# Adafruit_Feather_M0_Adalogger.net
KiCad netlist of a schematic drawn in EAGLE
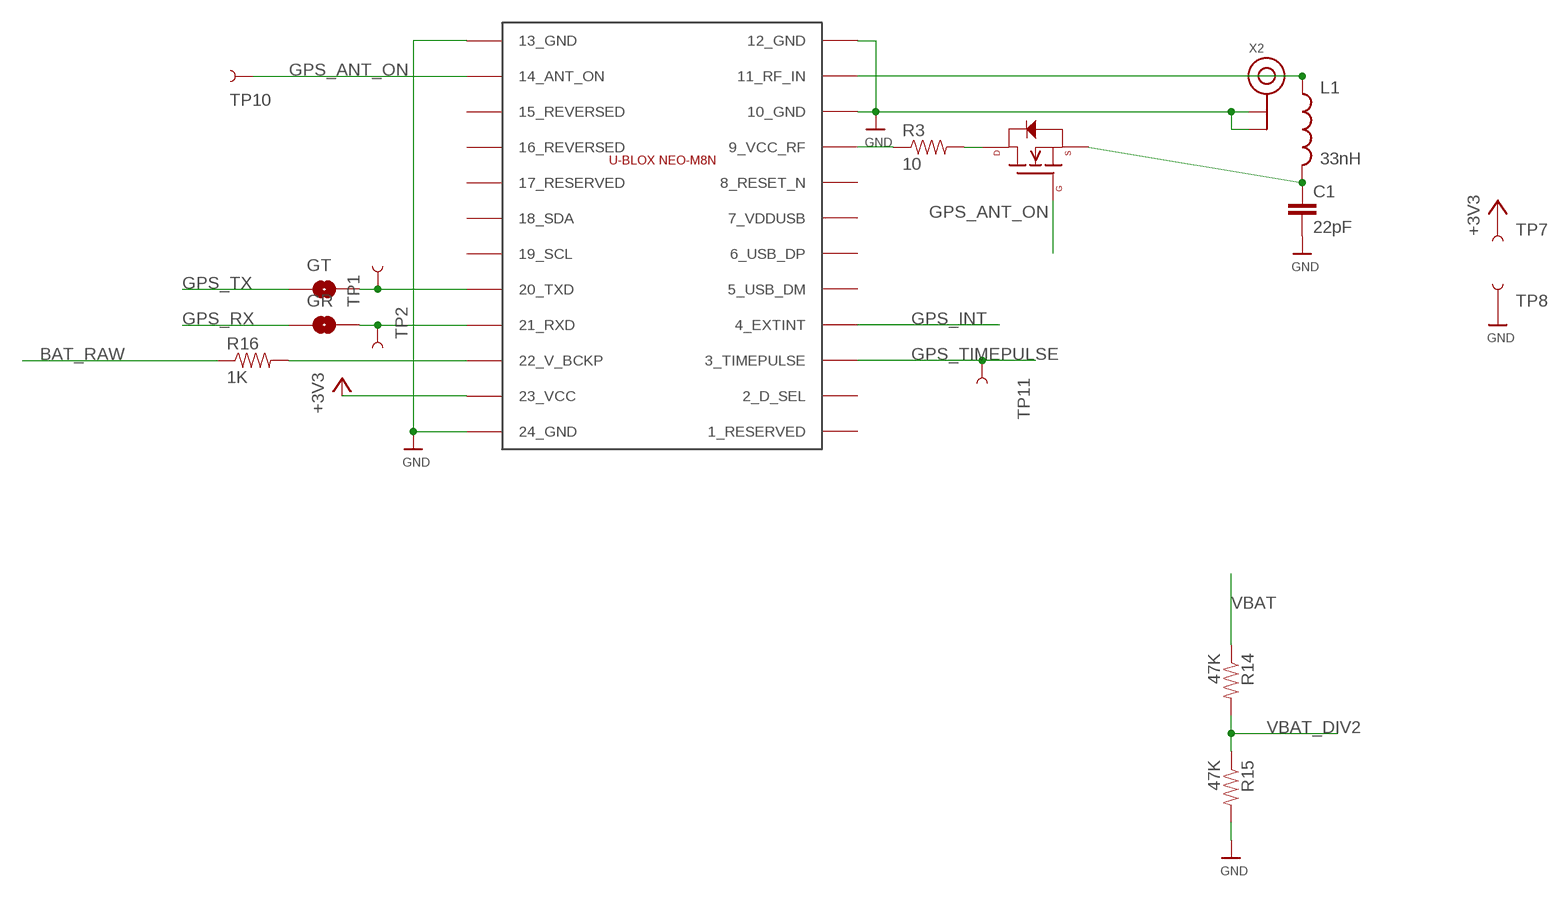
[diagram p0: schematic, sheet 1, part 1 of 2]
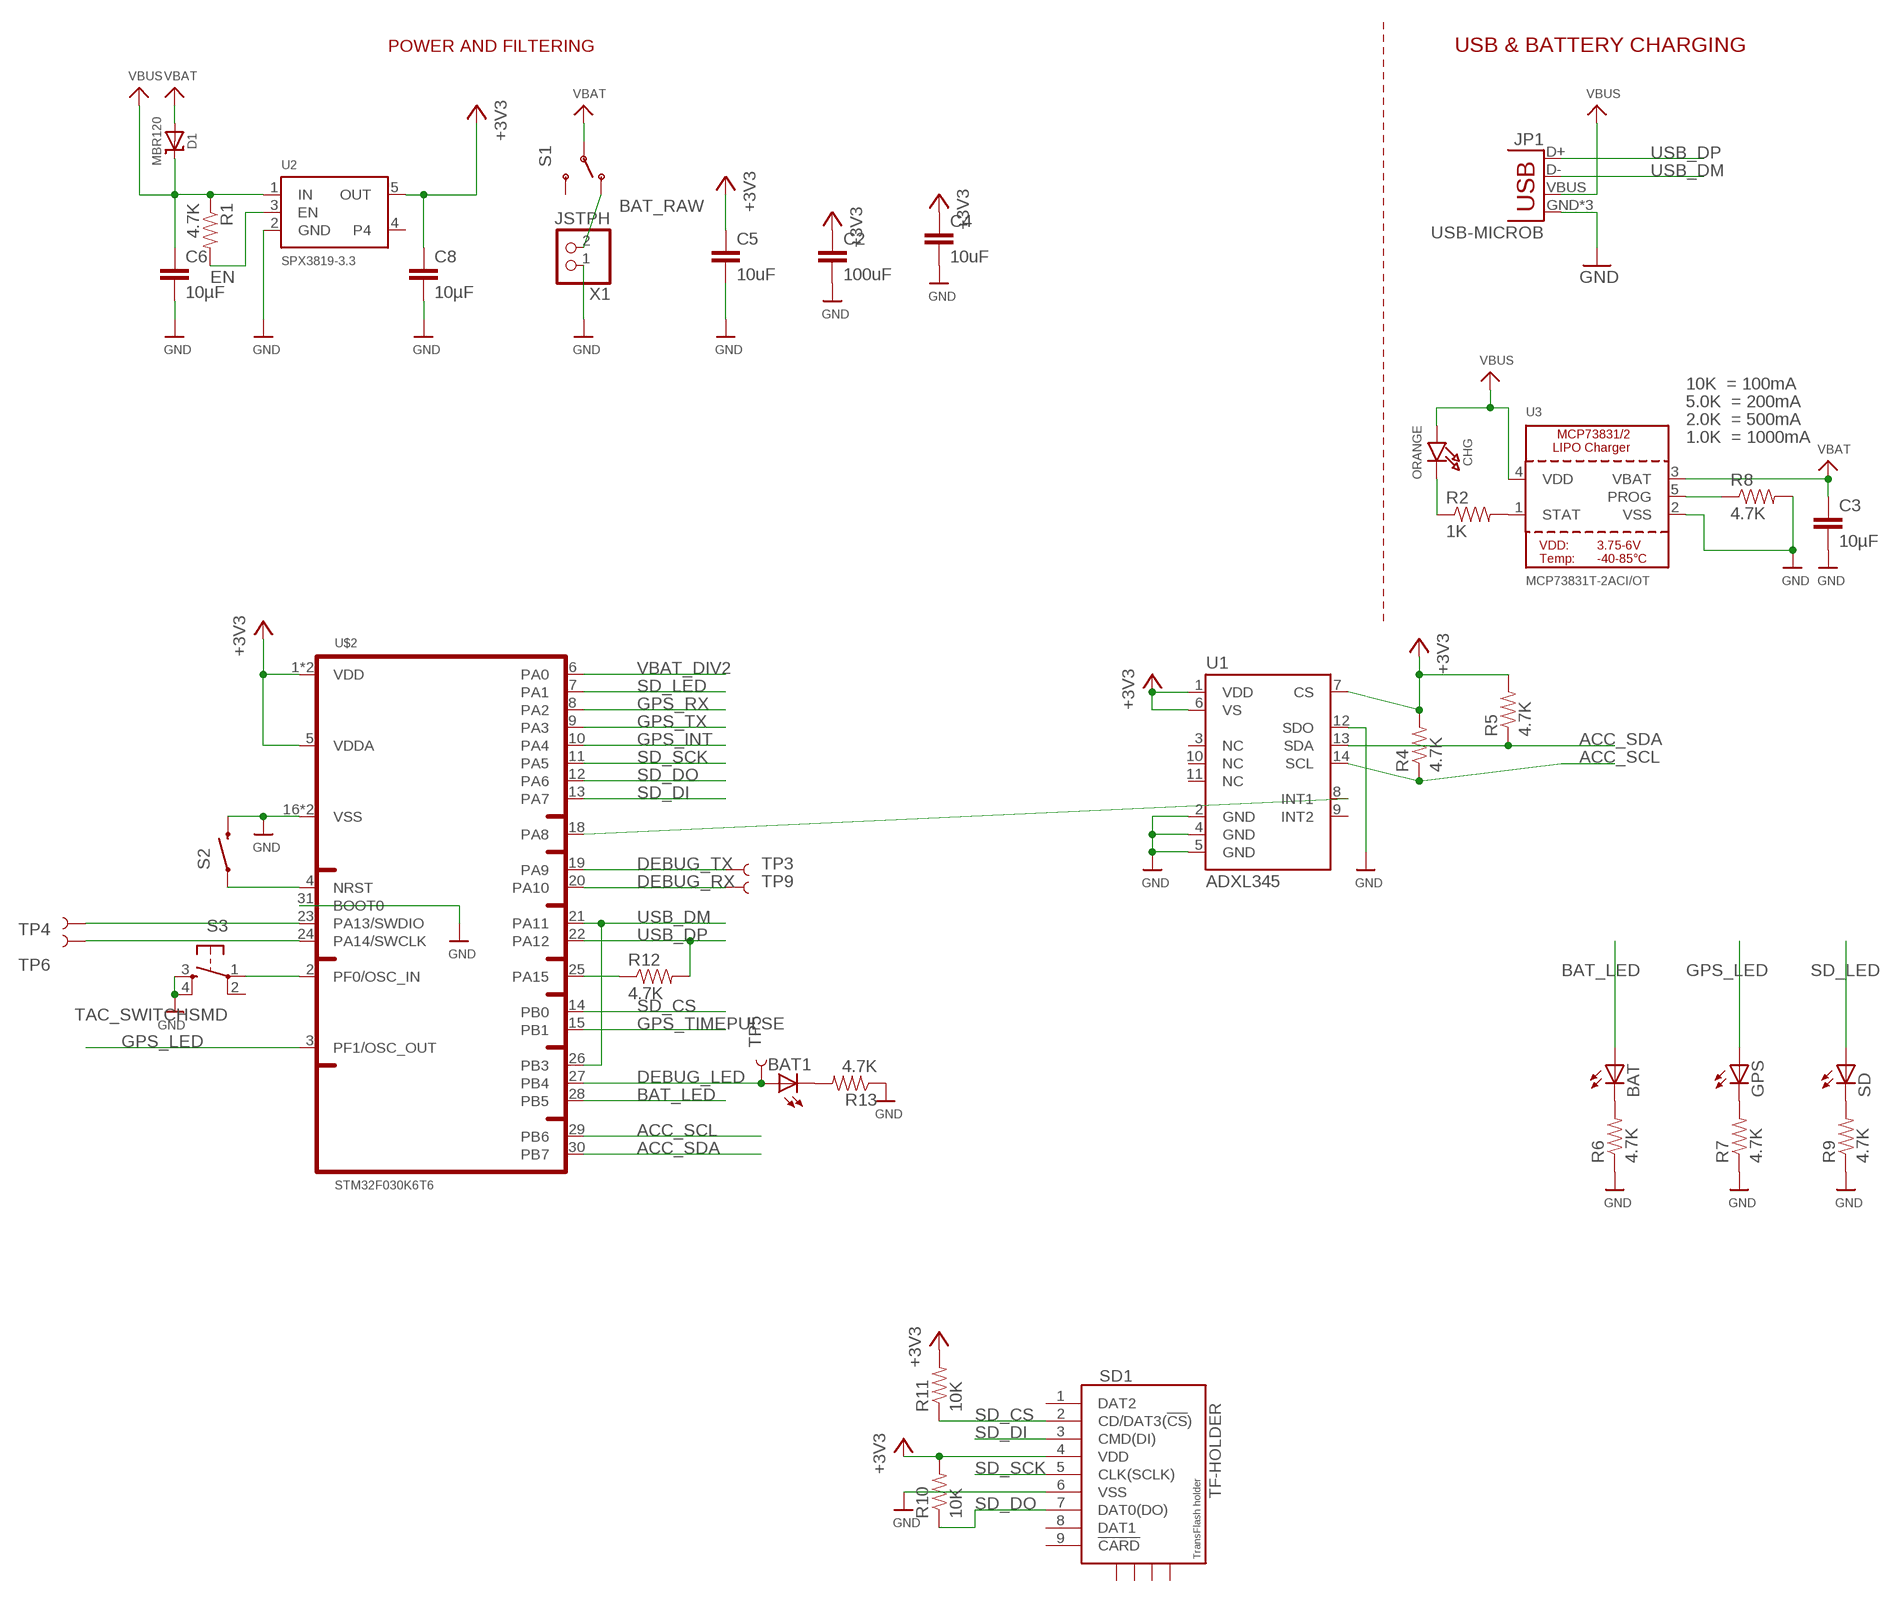
[diagram p1: schematic, sheet 1, part 2 of 2]

(export (version "E")
  (design (tool "Eeschema 10.0.6"))
  (components
    (comp (ref "BAT")
      (value "LEDCHIPLED_0805")
      (footprint "eagle-import:CHIPLED_0805")
      (libsource (lib "eagle-import") (part "LEDCHIPLED_0805"))
    )
    (comp (ref "BAT1")
      (value "LEDCHIPLED_0805")
      (footprint "eagle-import:CHIPLED_0805")
      (libsource (lib "eagle-import") (part "LEDCHIPLED_0805"))
    )
    (comp (ref "C1")
      (value "22pF")
      (footprint "eagle-import:0805")
      (libsource (lib "eagle-import") (part "CAP0805"))
    )
    (comp (ref "C2")
      (value "100uF")
      (footprint "eagle-import:1210")
      (libsource (lib "eagle-import") (part "100UF6.3V20%(1210)"))
    )
    (comp (ref "C3")
      (value "10µF")
      (footprint "eagle-import:0805")
      (libsource (lib "eagle-import") (part "CAP0805"))
    )
    (comp (ref "C4")
      (value "10uF")
      (footprint "eagle-import:0805")
      (libsource (lib "eagle-import") (part "CAP0805"))
    )
    (comp (ref "C5")
      (value "10uF")
      (footprint "eagle-import:0805")
      (libsource (lib "eagle-import") (part "CAP0805"))
    )
    (comp (ref "C6")
      (value "10µF")
      (footprint "eagle-import:0805")
      (libsource (lib "eagle-import") (part "CAP0805"))
    )
    (comp (ref "C8")
      (value "10µF")
      (footprint "eagle-import:0805")
      (libsource (lib "eagle-import") (part "CAP0805"))
    )
    (comp (ref "CHG")
      (value "ORANGE")
      (footprint "eagle-import:CHIPLED_0805_NOOUTLINE")
      (libsource (lib "eagle-import") (part "LED0805_NOOUTLINE"))
    )
    (comp (ref "D1")
      (value "MBR120")
      (footprint "eagle-import:SOD-123")
      (libsource (lib "eagle-import") (part "DIODE-SCHOTTKYSOD-123"))
    )
    (comp (ref "DEKU1")
      (value "UBLOX_NEO-M8N")
      (footprint "eagle-import:UBLOX_NEO-M8N")
      (libsource (lib "eagle-import") (part "UBLOX_NEO-M8N"))
    )
    (comp (ref "GPS")
      (value "LEDCHIPLED_0805")
      (footprint "eagle-import:CHIPLED_0805")
      (libsource (lib "eagle-import") (part "LEDCHIPLED_0805"))
    )
    (comp (ref "GR")
      (value "JUMPER-PAD-2-NO")
      (footprint "eagle-import:PAD-JUMPER-2-NO_NO_SILK")
      (libsource (lib "eagle-import") (part "JUMPER-PAD-2-NO"))
    )
    (comp (ref "GT")
      (value "JUMPER-PAD-2-NO")
      (footprint "eagle-import:PAD-JUMPER-2-NO_NO_SILK")
      (libsource (lib "eagle-import") (part "JUMPER-PAD-2-NO"))
    )
    (comp (ref "JP1")
      (value "USB-MICROB")
      (footprint "eagle-import:USB-MICROB")
      (libsource (lib "eagle-import") (part "USB-MICROB"))
    )
    (comp (ref "L1")
      (value "33nH")
      (footprint "eagle-import:0805")
      (libsource (lib "eagle-import") (part "INDUCTOR0805"))
    )
    (comp (ref "R1")
      (value "4.7K")
      (footprint "eagle-import:0805")
      (libsource (lib "eagle-import") (part "RESISTOR0805-RES"))
    )
    (comp (ref "R2")
      (value "1K")
      (footprint "eagle-import:0805")
      (libsource (lib "eagle-import") (part "RESISTOR0805-RES"))
    )
    (comp (ref "R3")
      (value "10")
      (footprint "eagle-import:0805")
      (libsource (lib "eagle-import") (part "RESISTOR0805-RES"))
    )
    (comp (ref "R4")
      (value "4.7K")
      (footprint "eagle-import:0805")
      (libsource (lib "eagle-import") (part "RESISTOR0805-RES"))
    )
    (comp (ref "R5")
      (value "4.7K")
      (footprint "eagle-import:0805")
      (libsource (lib "eagle-import") (part "RESISTOR0805-RES"))
    )
    (comp (ref "R6")
      (value "4.7K")
      (footprint "eagle-import:0805")
      (libsource (lib "eagle-import") (part "RESISTOR0805-RES"))
    )
    (comp (ref "R7")
      (value "4.7K")
      (footprint "eagle-import:0805")
      (libsource (lib "eagle-import") (part "RESISTOR0805-RES"))
    )
    (comp (ref "R8")
      (value "4.7K")
      (footprint "eagle-import:0805")
      (libsource (lib "eagle-import") (part "RESISTOR0805-RES"))
    )
    (comp (ref "R9")
      (value "4.7K")
      (footprint "eagle-import:0805")
      (libsource (lib "eagle-import") (part "RESISTOR0805-RES"))
    )
    (comp (ref "R10")
      (value "10K")
      (footprint "eagle-import:0805")
      (libsource (lib "eagle-import") (part "RESISTOR0805-RES"))
    )
    (comp (ref "R11")
      (value "10K")
      (footprint "eagle-import:0805")
      (libsource (lib "eagle-import") (part "RESISTOR0805-RES"))
    )
    (comp (ref "R12")
      (value "4.7K")
      (footprint "eagle-import:0805")
      (libsource (lib "eagle-import") (part "RESISTOR0805-RES"))
    )
    (comp (ref "R13")
      (value "4.7K")
      (footprint "eagle-import:0805")
      (libsource (lib "eagle-import") (part "RESISTOR0805-RES"))
    )
    (comp (ref "R14")
      (value "47K")
      (footprint "eagle-import:0805")
      (libsource (lib "eagle-import") (part "RESISTOR0805-RES"))
    )
    (comp (ref "R15")
      (value "47K")
      (footprint "eagle-import:0805")
      (libsource (lib "eagle-import") (part "RESISTOR0805-RES"))
    )
    (comp (ref "R16")
      (value "1K")
      (footprint "eagle-import:0805")
      (libsource (lib "eagle-import") (part "RESISTOR0805-RES"))
    )
    (comp (ref "S1")
      (value "SWITCH-SPDT-SMD-A")
      (footprint "eagle-import:SWITCH-SPST-SMD-A")
      (libsource (lib "eagle-import") (part "SWITCH-SPDT-SMD-A"))
    )
    (comp (ref "S2")
      (value "SWITCH-MOMENTARY-2TURTLE")
      (footprint "eagle-import:KMR2")
      (libsource (lib "eagle-import") (part "SWITCH-MOMENTARY-2TURTLE"))
    )
    (comp (ref "S3")
      (value "TAC_SWITCHSMD")
      (footprint "eagle-import:TACTILE-SWITCH-SMD")
      (libsource (lib "eagle-import") (part "TAC_SWITCHSMD"))
    )
    (comp (ref "SD")
      (value "LEDCHIPLED_0805")
      (footprint "eagle-import:CHIPLED_0805")
      (libsource (lib "eagle-import") (part "LEDCHIPLED_0805"))
    )
    (comp (ref "SD1")
      (value "TF-HOLDER")
      (footprint "eagle-import:TF-PULL")
      (libsource (lib "eagle-import") (part "TF-HOLDER"))
    )
    (comp (ref "TP1")
      (value "TEST-POINT3X5")
      (footprint "eagle-import:PAD.03X.05")
      (libsource (lib "eagle-import") (part "TEST-POINT3X5"))
    )
    (comp (ref "TP2")
      (value "TEST-POINT3X5")
      (footprint "eagle-import:PAD.03X.05")
      (libsource (lib "eagle-import") (part "TEST-POINT3X5"))
    )
    (comp (ref "TP3")
      (value "TEST-POINT3X5")
      (footprint "eagle-import:PAD.03X.05")
      (libsource (lib "eagle-import") (part "TEST-POINT3X5"))
    )
    (comp (ref "TP4")
      (value "TEST-POINT3X5")
      (footprint "eagle-import:PAD.03X.05")
      (libsource (lib "eagle-import") (part "TEST-POINT3X5"))
    )
    (comp (ref "TP5")
      (value "TEST-POINT3X5")
      (footprint "eagle-import:PAD.03X.05")
      (libsource (lib "eagle-import") (part "TEST-POINT3X5"))
    )
    (comp (ref "TP6")
      (value "TEST-POINT3X5")
      (footprint "eagle-import:PAD.03X.05")
      (libsource (lib "eagle-import") (part "TEST-POINT3X5"))
    )
    (comp (ref "TP7")
      (value "TEST-POINT3X5")
      (footprint "eagle-import:PAD.03X.05")
      (libsource (lib "eagle-import") (part "TEST-POINT3X5"))
    )
    (comp (ref "TP8")
      (value "TEST-POINT3X5")
      (footprint "eagle-import:PAD.03X.05")
      (libsource (lib "eagle-import") (part "TEST-POINT3X5"))
    )
    (comp (ref "TP9")
      (value "TEST-POINT3X5")
      (footprint "eagle-import:PAD.03X.05")
      (libsource (lib "eagle-import") (part "TEST-POINT3X5"))
    )
    (comp (ref "TP10")
      (value "TEST-POINT3X5")
      (footprint "eagle-import:PAD.03X.05")
      (libsource (lib "eagle-import") (part "TEST-POINT3X5"))
    )
    (comp (ref "TP11")
      (value "TEST-POINT3X5")
      (footprint "eagle-import:PAD.03X.05")
      (libsource (lib "eagle-import") (part "TEST-POINT3X5"))
    )
    (comp (ref "U$2")
      (value "STM32F030K6T6")
      (footprint "eagle-import:TQFP32-08")
      (libsource (lib "eagle-import") (part "STM32F030K6T6"))
    )
    (comp (ref "U$24")
      (value "N-CHANNEL-MOSFET-BSS138")
      (footprint "eagle-import:SOT23-3")
      (libsource (lib "eagle-import") (part "N-CHANNEL-MOSFET-BSS138"))
    )
    (comp (ref "U1")
      (value "ADXL345")
      (footprint "eagle-import:LGA14")
      (libsource (lib "eagle-import") (part "ADXL345"))
    )
    (comp (ref "U2")
      (value "SPX3819-3.3")
      (footprint "eagle-import:SOT23-5")
      (libsource (lib "eagle-import") (part "VREG_SOT23-5"))
    )
    (comp (ref "U3")
      (value "MCP73831T-2ACI/OT")
      (footprint "eagle-import:SOT23-5")
      (libsource (lib "eagle-import") (part "MCP73831/2"))
    )
    (comp (ref "X1")
      (value "JSTPH")
      (footprint "eagle-import:JSTPH2")
      (libsource (lib "eagle-import") (part "CON_JST_PH_2PIN"))
    )
    (comp (ref "X2")
      (value "ANTENNA_U.FL")
      (footprint "eagle-import:U.FL")
      (libsource (lib "eagle-import") (part "ANTENNA_U.FL"))
    )
  )
  (nets
    (net (code "1") (name "+3V3") (class "Default")
      (node (ref "C2") (pin "1") (pinfunction "1_1") (pintype "passive"))
      (node (ref "C4") (pin "1") (pinfunction "1_1") (pintype "passive"))
      (node (ref "C5") (pin "1") (pinfunction "1_1") (pintype "passive"))
      (node (ref "C8") (pin "1") (pinfunction "1_1") (pintype "passive"))
      (node (ref "DEKU1") (pin "23_VCC") (pinfunction "23_VCC_23_VCC") (pintype "bidirectional"))
      (node (ref "R10") (pin "2") (pinfunction "2_2") (pintype "passive"))
      (node (ref "R11") (pin "2") (pinfunction "2_2") (pintype "passive"))
      (node (ref "R4") (pin "2") (pinfunction "2_2") (pintype "passive"))
      (node (ref "R5") (pin "2") (pinfunction "2_2") (pintype "passive"))
      (node (ref "SD1") (pin "4") (pinfunction "VDD_4") (pintype "power_in"))
      (node (ref "TP7") (pin "P$1") (pinfunction "1_P$1") (pintype "bidirectional"))
      (node (ref "U$2") (pin "1") (pinfunction "VDD_1") (pintype "bidirectional"))
      (node (ref "U$2") (pin "17") (pinfunction "VDD_17") (pintype "bidirectional"))
      (node (ref "U$2") (pin "5") (pinfunction "VDDA_5") (pintype "bidirectional"))
      (node (ref "U1") (pin "1") (pinfunction "VDD_1") (pintype "bidirectional"))
      (node (ref "U1") (pin "6") (pinfunction "VS_6") (pintype "bidirectional"))
      (node (ref "U1") (pin "7") (pinfunction "CS_7") (pintype "bidirectional"))
      (node (ref "U2") (pin "5") (pinfunction "OUT_5") (pintype "power_in"))
    )
    (net (code "2") (name "/ACC_SCL") (class "Default")
      (node (ref "R4") (pin "1") (pinfunction "1_1") (pintype "passive"))
      (node (ref "U$2") (pin "29") (pinfunction "PB6_29") (pintype "bidirectional"))
      (node (ref "U1") (pin "14") (pinfunction "SCL_14") (pintype "bidirectional"))
    )
    (net (code "3") (name "/ACC_SDA") (class "Default")
      (node (ref "R5") (pin "1") (pinfunction "1_1") (pintype "passive"))
      (node (ref "U$2") (pin "30") (pinfunction "PB7_30") (pintype "bidirectional"))
      (node (ref "U1") (pin "13") (pinfunction "SDA_13") (pintype "bidirectional"))
    )
    (net (code "4") (name "/BAT_LED") (class "Default")
      (node (ref "BAT") (pin "A") (pinfunction "A_A") (pintype "passive"))
      (node (ref "U$2") (pin "28") (pinfunction "PB5_28") (pintype "bidirectional"))
    )
    (net (code "5") (name "/BAT_RAW") (class "Default")
      (node (ref "R16") (pin "1") (pinfunction "1_1") (pintype "passive"))
      (node (ref "S1") (pin "1") (pinfunction "O_1") (pintype "passive"))
      (node (ref "X1") (pin "2") (pinfunction "2_2") (pintype "passive"))
    )
    (net (code "6") (name "/DEBUG_LED") (class "Default")
      (node (ref "BAT1") (pin "A") (pinfunction "A_A") (pintype "passive"))
      (node (ref "TP5") (pin "P$1") (pinfunction "1_P$1") (pintype "bidirectional"))
      (node (ref "U$2") (pin "27") (pinfunction "PB4_27") (pintype "bidirectional"))
    )
    (net (code "7") (name "/DEBUG_RX") (class "Default")
      (node (ref "TP9") (pin "P$1") (pinfunction "1_P$1") (pintype "bidirectional"))
      (node (ref "U$2") (pin "20") (pinfunction "PA10_20") (pintype "bidirectional"))
    )
    (net (code "8") (name "/DEBUG_TX") (class "Default")
      (node (ref "TP3") (pin "P$1") (pinfunction "1_P$1") (pintype "bidirectional"))
      (node (ref "U$2") (pin "19") (pinfunction "PA9_19") (pintype "bidirectional"))
    )
    (net (code "9") (name "/EN") (class "Default")
      (node (ref "R1") (pin "2") (pinfunction "2_2") (pintype "passive"))
      (node (ref "U2") (pin "3") (pinfunction "EN_3") (pintype "input"))
    )
    (net (code "10") (name "/GPS_ANT_ON") (class "Default")
      (node (ref "DEKU1") (pin "14_ANT_ON") (pinfunction "14_ANT_ON_14_ANT_ON") (pintype "bidirectional"))
      (node (ref "TP10") (pin "P$1") (pinfunction "1_P$1") (pintype "bidirectional"))
      (node (ref "U$24") (pin "1") (pinfunction "G_1") (pintype "passive"))
    )
    (net (code "11") (name "/GPS_INT") (class "Default")
      (node (ref "DEKU1") (pin "4_EXTINT") (pinfunction "4_EXTINT_4_EXTINT") (pintype "bidirectional"))
      (node (ref "U$2") (pin "10") (pinfunction "PA4_10") (pintype "bidirectional"))
    )
    (net (code "12") (name "/GPS_LED") (class "Default")
      (node (ref "GPS") (pin "A") (pinfunction "A_A") (pintype "passive"))
      (node (ref "U$2") (pin "3") (pinfunction "PF1/OSC_OUT_3") (pintype "bidirectional"))
    )
    (net (code "13") (name "/GPS_RX") (class "Default")
      (node (ref "GR") (pin "1") (pinfunction "1_1") (pintype "passive"))
      (node (ref "U$2") (pin "8") (pinfunction "PA2_8") (pintype "bidirectional"))
    )
    (net (code "14") (name "/GPS_TIMEPULSE") (class "Default")
      (node (ref "DEKU1") (pin "3_TIMEPULSE") (pinfunction "3_TIMEPULSE_3_TIMEPULSE") (pintype "bidirectional"))
      (node (ref "TP11") (pin "P$1") (pinfunction "1_P$1") (pintype "bidirectional"))
      (node (ref "U$2") (pin "15") (pinfunction "PB1_15") (pintype "bidirectional"))
    )
    (net (code "15") (name "/GPS_TX") (class "Default")
      (node (ref "GT") (pin "1") (pinfunction "1_1") (pintype "passive"))
      (node (ref "U$2") (pin "9") (pinfunction "PA3_9") (pintype "bidirectional"))
    )
    (net (code "16") (name "/SD_CS") (class "Default")
      (node (ref "R11") (pin "1") (pinfunction "1_1") (pintype "passive"))
      (node (ref "SD1") (pin "2") (pinfunction "CD/DAT3(~{CS})_2") (pintype "bidirectional"))
      (node (ref "U$2") (pin "14") (pinfunction "PB0_14") (pintype "bidirectional"))
    )
    (net (code "17") (name "/SD_DI") (class "Default")
      (node (ref "SD1") (pin "3") (pinfunction "CMD(DI)_3") (pintype "bidirectional"))
      (node (ref "U$2") (pin "13") (pinfunction "PA7_13") (pintype "bidirectional"))
    )
    (net (code "18") (name "/SD_DO") (class "Default")
      (node (ref "R10") (pin "1") (pinfunction "1_1") (pintype "passive"))
      (node (ref "SD1") (pin "7") (pinfunction "DAT0(DO)_7") (pintype "bidirectional"))
      (node (ref "U$2") (pin "12") (pinfunction "PA6_12") (pintype "bidirectional"))
    )
    (net (code "19") (name "/SD_LED") (class "Default")
      (node (ref "SD") (pin "A") (pinfunction "A_A") (pintype "passive"))
      (node (ref "U$2") (pin "7") (pinfunction "PA1_7") (pintype "bidirectional"))
    )
    (net (code "20") (name "/SD_SCK") (class "Default")
      (node (ref "SD1") (pin "5") (pinfunction "CLK(SCLK)_5") (pintype "input"))
      (node (ref "U$2") (pin "11") (pinfunction "PA5_11") (pintype "bidirectional"))
    )
    (net (code "21") (name "/USB_DM") (class "Default")
      (node (ref "JP1") (pin "D-") (pinfunction "D-_D-") (pintype "bidirectional"))
      (node (ref "U$2") (pin "21") (pinfunction "PA11_21") (pintype "bidirectional"))
      (node (ref "U$2") (pin "26") (pinfunction "PB3_26") (pintype "bidirectional"))
    )
    (net (code "22") (name "/USB_DP") (class "Default")
      (node (ref "JP1") (pin "D+") (pinfunction "D+_D+") (pintype "bidirectional"))
      (node (ref "R12") (pin "2") (pinfunction "2_2") (pintype "passive"))
      (node (ref "U$2") (pin "22") (pinfunction "PA12_22") (pintype "bidirectional"))
    )
    (net (code "23") (name "/VBAT_DIV2") (class "Default")
      (node (ref "R14") (pin "2") (pinfunction "2_2") (pintype "passive"))
      (node (ref "R15") (pin "1") (pinfunction "1_1") (pintype "passive"))
      (node (ref "U$2") (pin "6") (pinfunction "PA0_6") (pintype "bidirectional"))
    )
    (net (code "24") (name "GND") (class "Default")
      (node (ref "C1") (pin "2") (pinfunction "2_2") (pintype "passive"))
      (node (ref "C2") (pin "2") (pinfunction "2_2") (pintype "passive"))
      (node (ref "C3") (pin "2") (pinfunction "2_2") (pintype "passive"))
      (node (ref "C4") (pin "2") (pinfunction "2_2") (pintype "passive"))
      (node (ref "C5") (pin "2") (pinfunction "2_2") (pintype "passive"))
      (node (ref "C6") (pin "2") (pinfunction "2_2") (pintype "passive"))
      (node (ref "C8") (pin "2") (pinfunction "2_2") (pintype "passive"))
      (node (ref "DEKU1") (pin "10_GND") (pinfunction "10_GND_10_GND") (pintype "bidirectional"))
      (node (ref "DEKU1") (pin "12_GND") (pinfunction "12_GND_12_GND") (pintype "bidirectional"))
      (node (ref "DEKU1") (pin "13_GND") (pinfunction "13_GND_13_GND") (pintype "bidirectional"))
      (node (ref "DEKU1") (pin "24_GND") (pinfunction "24_GND_24_GND") (pintype "bidirectional"))
      (node (ref "JP1") (pin "GND") (pinfunction "GND_GND") (pintype "bidirectional"))
      (node (ref "JP1") (pin "MT1") (pinfunction "GND_MT1") (pintype "bidirectional"))
      (node (ref "JP1") (pin "MT2") (pinfunction "GND_MT2") (pintype "bidirectional"))
      (node (ref "R13") (pin "1") (pinfunction "1_1") (pintype "passive"))
      (node (ref "R15") (pin "2") (pinfunction "2_2") (pintype "passive"))
      (node (ref "R6") (pin "1") (pinfunction "1_1") (pintype "passive"))
      (node (ref "R7") (pin "1") (pinfunction "1_1") (pintype "passive"))
      (node (ref "R8") (pin "2") (pinfunction "2_2") (pintype "passive"))
      (node (ref "R9") (pin "1") (pinfunction "1_1") (pintype "passive"))
      (node (ref "S2") (pin "3") (pinfunction "2_3") (pintype "passive"))
      (node (ref "S3") (pin "3") (pinfunction "3_3") (pintype "passive"))
      (node (ref "S3") (pin "4") (pinfunction "4_4") (pintype "passive"))
      (node (ref "SD1") (pin "6") (pinfunction "VSS_6") (pintype "power_in"))
      (node (ref "TP8") (pin "P$1") (pinfunction "1_P$1") (pintype "bidirectional"))
      (node (ref "U$2") (pin "16") (pinfunction "VSS_16") (pintype "bidirectional"))
      (node (ref "U$2") (pin "31") (pinfunction "BOOT0_31") (pintype "bidirectional"))
      (node (ref "U$2") (pin "32") (pinfunction "VSS_32") (pintype "bidirectional"))
      (node (ref "U1") (pin "12") (pinfunction "SDO_12") (pintype "bidirectional"))
      (node (ref "U1") (pin "2") (pinfunction "GND_2") (pintype "bidirectional"))
      (node (ref "U1") (pin "4") (pinfunction "GND_4") (pintype "bidirectional"))
      (node (ref "U1") (pin "5") (pinfunction "GND_5") (pintype "bidirectional"))
      (node (ref "U2") (pin "2") (pinfunction "GND_2") (pintype "power_in"))
      (node (ref "U3") (pin "2") (pinfunction "VSS_2") (pintype "power_in"))
      (node (ref "X1") (pin "1") (pinfunction "1_1") (pintype "passive"))
      (node (ref "X2") (pin "1") (pinfunction "GND_1") (pintype "passive"))
      (node (ref "X2") (pin "2") (pinfunction "GND_2") (pintype "passive"))
    )
    (net (code "25") (name "Net-(BAT-PadC)") (class "Default")
      (node (ref "BAT") (pin "C") (pinfunction "C_C") (pintype "passive"))
      (node (ref "R6") (pin "2") (pinfunction "2_2") (pintype "passive"))
    )
    (net (code "26") (name "Net-(BAT1-PadC)") (class "Default")
      (node (ref "BAT1") (pin "C") (pinfunction "C_C") (pintype "passive"))
      (node (ref "R13") (pin "2") (pinfunction "2_2") (pintype "passive"))
    )
    (net (code "27") (name "Net-(CHG-PadC)") (class "Default")
      (node (ref "CHG") (pin "C") (pinfunction "C_C") (pintype "passive"))
      (node (ref "R2") (pin "1") (pinfunction "1_1") (pintype "passive"))
    )
    (net (code "28") (name "Net-(DEKU1-Pad9_VCC_RF)") (class "Default")
      (node (ref "DEKU1") (pin "9_VCC_RF") (pinfunction "9_VCC_RF_9_VCC_RF") (pintype "bidirectional"))
      (node (ref "R3") (pin "1") (pinfunction "1_1") (pintype "passive"))
    )
    (net (code "29") (name "Net-(DEKU1-Pad22_V_BCKP)") (class "Default")
      (node (ref "DEKU1") (pin "22_V_BCKP") (pinfunction "22_V_BCKP_22_V_BCKP") (pintype "bidirectional"))
      (node (ref "R16") (pin "2") (pinfunction "2_2") (pintype "passive"))
    )
    (net (code "30") (name "Net-(GPS-PadC)") (class "Default")
      (node (ref "GPS") (pin "C") (pinfunction "C_C") (pintype "passive"))
      (node (ref "R7") (pin "2") (pinfunction "2_2") (pintype "passive"))
    )
    (net (code "31") (name "Net-(R9-Pad2)") (class "Default")
      (node (ref "R9") (pin "2") (pinfunction "2_2") (pintype "passive"))
      (node (ref "SD") (pin "C") (pinfunction "C_C") (pintype "passive"))
    )
    (net (code "32") (name "Net-(TP1-1)") (class "Default")
      (node (ref "DEKU1") (pin "20_TXD") (pinfunction "20_TXD_20_TXD") (pintype "bidirectional"))
      (node (ref "GT") (pin "2") (pinfunction "2_2") (pintype "passive"))
      (node (ref "TP1") (pin "P$1") (pinfunction "1_P$1") (pintype "bidirectional"))
    )
    (net (code "33") (name "Net-(TP2-1)") (class "Default")
      (node (ref "DEKU1") (pin "21_RXD") (pinfunction "21_RXD_21_RXD") (pintype "bidirectional"))
      (node (ref "GR") (pin "2") (pinfunction "2_2") (pintype "passive"))
      (node (ref "TP2") (pin "P$1") (pinfunction "1_P$1") (pintype "bidirectional"))
    )
    (net (code "34") (name "Net-(TP4-1)") (class "Default")
      (node (ref "TP4") (pin "P$1") (pinfunction "1_P$1") (pintype "bidirectional"))
      (node (ref "U$2") (pin "23") (pinfunction "PA13/SWDIO_23") (pintype "bidirectional"))
    )
    (net (code "35") (name "Net-(TP6-1)") (class "Default")
      (node (ref "TP6") (pin "P$1") (pinfunction "1_P$1") (pintype "bidirectional"))
      (node (ref "U$2") (pin "24") (pinfunction "PA14/SWCLK_24") (pintype "bidirectional"))
    )
    (net (code "36") (name "Net-(U$2-NRST)") (class "Default")
      (node (ref "S2") (pin "1") (pinfunction "1_1") (pintype "passive"))
      (node (ref "U$2") (pin "4") (pinfunction "NRST_4") (pintype "bidirectional"))
    )
    (net (code "37") (name "Net-(U$2-PA8)") (class "Default")
      (node (ref "U$2") (pin "18") (pinfunction "PA8_18") (pintype "bidirectional"))
      (node (ref "U1") (pin "8") (pinfunction "INT1_8") (pintype "bidirectional"))
    )
    (net (code "38") (name "Net-(U$2-PA15)") (class "Default")
      (node (ref "R12") (pin "1") (pinfunction "1_1") (pintype "passive"))
      (node (ref "U$2") (pin "25") (pinfunction "PA15_25") (pintype "bidirectional"))
    )
    (net (code "39") (name "Net-(U$2-PF0{slash}OSC_IN)") (class "Default")
      (node (ref "S3") (pin "1") (pinfunction "1_1") (pintype "passive"))
      (node (ref "U$2") (pin "2") (pinfunction "PF0/OSC_IN_2") (pintype "bidirectional"))
    )
    (net (code "40") (name "Net-(U$24-D)") (class "Default")
      (node (ref "R3") (pin "2") (pinfunction "2_2") (pintype "passive"))
      (node (ref "U$24") (pin "3") (pinfunction "D_3") (pintype "passive"))
    )
    (net (code "41") (name "Net-(U$24-S)") (class "Default")
      (node (ref "C1") (pin "1") (pinfunction "1_1") (pintype "passive"))
      (node (ref "L1") (pin "2") (pinfunction "2_2") (pintype "passive"))
      (node (ref "U$24") (pin "2") (pinfunction "S_2") (pintype "passive"))
    )
    (net (code "42") (name "Net-(U3-PROG)") (class "Default")
      (node (ref "R8") (pin "1") (pinfunction "1_1") (pintype "passive"))
      (node (ref "U3") (pin "5") (pinfunction "PROG_5") (pintype "input"))
    )
    (net (code "43") (name "Net-(U3-STAT)") (class "Default")
      (node (ref "R2") (pin "2") (pinfunction "2_2") (pintype "passive"))
      (node (ref "U3") (pin "1") (pinfunction "STAT_1") (pintype "output"))
    )
    (net (code "44") (name "Net-(X2-SIGNAL)") (class "Default")
      (node (ref "DEKU1") (pin "11_RF_IN") (pinfunction "11_RF_IN_11_RF_IN") (pintype "bidirectional"))
      (node (ref "L1") (pin "1") (pinfunction "1_1") (pintype "passive"))
      (node (ref "X2") (pin "3") (pinfunction "SIGNAL_3") (pintype "passive"))
    )
    (net (code "45") (name "VBAT") (class "Default")
      (node (ref "C3") (pin "1") (pinfunction "1_1") (pintype "passive"))
      (node (ref "D1") (pin "A") (pinfunction "A_A") (pintype "passive"))
      (node (ref "R14") (pin "1") (pinfunction "1_1") (pintype "passive"))
      (node (ref "S1") (pin "2") (pinfunction "P_2") (pintype "passive"))
      (node (ref "U3") (pin "3") (pinfunction "VBAT_3") (pintype "power_in"))
    )
    (net (code "46") (name "VBUS") (class "Default")
      (node (ref "C6") (pin "1") (pinfunction "1_1") (pintype "passive"))
      (node (ref "CHG") (pin "A") (pinfunction "A_A") (pintype "passive"))
      (node (ref "D1") (pin "C") (pinfunction "C_C") (pintype "passive"))
      (node (ref "JP1") (pin "VBUS") (pinfunction "VBUS_VBUS") (pintype "bidirectional"))
      (node (ref "R1") (pin "1") (pinfunction "1_1") (pintype "passive"))
      (node (ref "U2") (pin "1") (pinfunction "IN_1") (pintype "power_in"))
      (node (ref "U3") (pin "4") (pinfunction "VDD_4") (pintype "power_in"))
    )
    (net (code "47") (name "unconnected-(DEKU1-Pad1_RESERVED)") (class "Default")
      (node (ref "DEKU1") (pin "1_RESERVED") (pinfunction "1_RESERVED_1_RESERVED") (pintype "bidirectional"))
    )
    (net (code "48") (name "unconnected-(DEKU1-Pad2_D_SEL)") (class "Default")
      (node (ref "DEKU1") (pin "2_D_SEL") (pinfunction "2_D_SEL_2_D_SEL") (pintype "bidirectional"))
    )
    (net (code "49") (name "unconnected-(DEKU1-Pad5_USB_DM)") (class "Default")
      (node (ref "DEKU1") (pin "5_USB_DM") (pinfunction "5_USB_DM_5_USB_DM") (pintype "bidirectional"))
    )
    (net (code "50") (name "unconnected-(DEKU1-Pad6_USB_DP)") (class "Default")
      (node (ref "DEKU1") (pin "6_USB_DP") (pinfunction "6_USB_DP_6_USB_DP") (pintype "bidirectional"))
    )
    (net (code "51") (name "unconnected-(DEKU1-Pad7_VDDUSB)") (class "Default")
      (node (ref "DEKU1") (pin "7_VDDUSB") (pinfunction "7_VDDUSB_7_VDDUSB") (pintype "bidirectional"))
    )
    (net (code "52") (name "unconnected-(DEKU1-Pad8_RESET_N)") (class "Default")
      (node (ref "DEKU1") (pin "8_RESET_N") (pinfunction "8_RESET_N_8_RESET_N") (pintype "bidirectional"))
    )
    (net (code "53") (name "unconnected-(DEKU1-Pad15_REVERSED)") (class "Default")
      (node (ref "DEKU1") (pin "15_REVERSED") (pinfunction "15_REVERSED_15_REVERSED") (pintype "bidirectional"))
    )
    (net (code "54") (name "unconnected-(DEKU1-Pad16_REVERSED)") (class "Default")
      (node (ref "DEKU1") (pin "16_REVERSED") (pinfunction "16_REVERSED_16_REVERSED") (pintype "bidirectional"))
    )
    (net (code "55") (name "unconnected-(DEKU1-Pad17_RESERVED)") (class "Default")
      (node (ref "DEKU1") (pin "17_RESERVED") (pinfunction "17_RESERVED_17_RESERVED") (pintype "bidirectional"))
    )
    (net (code "56") (name "unconnected-(DEKU1-Pad18_SDA)") (class "Default")
      (node (ref "DEKU1") (pin "18_SDA") (pinfunction "18_SDA_18_SDA") (pintype "bidirectional"))
    )
    (net (code "57") (name "unconnected-(DEKU1-Pad19_SCL)") (class "Default")
      (node (ref "DEKU1") (pin "19_SCL") (pinfunction "19_SCL_19_SCL") (pintype "bidirectional"))
    )
    (net (code "58") (name "unconnected-(S1-S-Pad3)") (class "Default")
      (node (ref "S1") (pin "3") (pinfunction "S_3") (pintype "passive"))
    )
    (net (code "59") (name "unconnected-(S3-Pad2)") (class "Default")
      (node (ref "S3") (pin "2") (pinfunction "2_2") (pintype "passive"))
    )
    (net (code "60") (name "unconnected-(SD1-DAT1-Pad8)") (class "Default")
      (node (ref "SD1") (pin "8") (pinfunction "DAT1_8") (pintype "bidirectional"))
    )
    (net (code "61") (name "unconnected-(SD1-DAT2-Pad1)") (class "Default")
      (node (ref "SD1") (pin "1") (pinfunction "DAT2_1") (pintype "bidirectional"))
    )
    (net (code "62") (name "unconnected-(SD1-PadS1)") (class "Default")
      (node (ref "SD1") (pin "S1") (pinfunction "S1_S1") (pintype "passive"))
    )
    (net (code "63") (name "unconnected-(SD1-PadS2)") (class "Default")
      (node (ref "SD1") (pin "S2") (pinfunction "S2_S2") (pintype "passive"))
    )
    (net (code "64") (name "unconnected-(SD1-PadS3)") (class "Default")
      (node (ref "SD1") (pin "S3") (pinfunction "S3_S3") (pintype "passive"))
    )
    (net (code "65") (name "unconnected-(SD1-PadS4)") (class "Default")
      (node (ref "SD1") (pin "S4") (pinfunction "S4_S4") (pintype "passive"))
    )
    (net (code "66") (name "unconnected-(SD1-~{CARD}-Pad9)") (class "Default")
      (node (ref "SD1") (pin "9") (pinfunction "~{CARD}_9") (pintype "passive"))
    )
    (net (code "67") (name "unconnected-(U1-INT2-Pad9)") (class "Default")
      (node (ref "U1") (pin "9") (pinfunction "INT2_9") (pintype "bidirectional"))
    )
    (net (code "68") (name "unconnected-(U1-NC-Pad3)") (class "Default")
      (node (ref "U1") (pin "3") (pinfunction "NC_3") (pintype "bidirectional"))
    )
    (net (code "69") (name "unconnected-(U1-NC-Pad10)") (class "Default")
      (node (ref "U1") (pin "10") (pinfunction "NC_10") (pintype "bidirectional"))
    )
    (net (code "70") (name "unconnected-(U1-NC-Pad11)") (class "Default")
      (node (ref "U1") (pin "11") (pinfunction "NC_11") (pintype "bidirectional"))
    )
    (net (code "71") (name "unconnected-(U2-P4-Pad4)") (class "Default")
      (node (ref "U2") (pin "4") (pinfunction "P4_4") (pintype "bidirectional"))
    )
  )
)
